# PowerMisc.net
KiCad netlist of a schematic drawn in Altium Designer
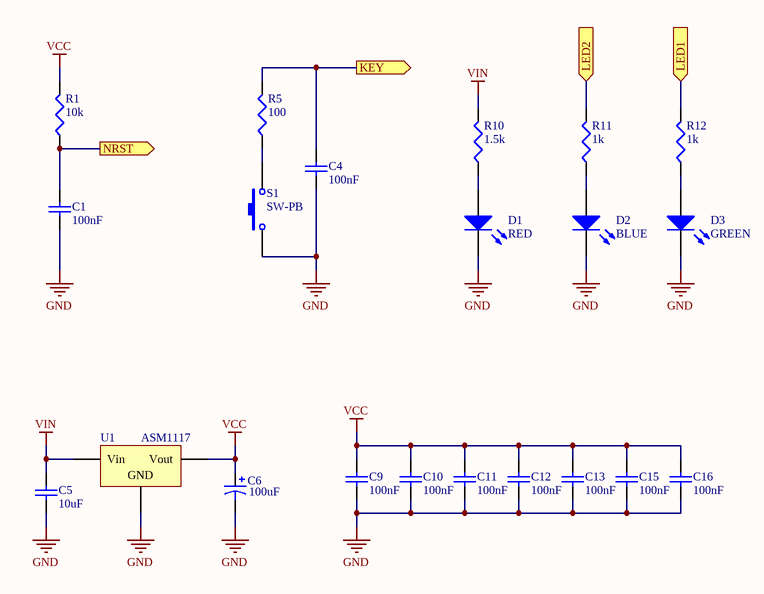
[diagram p0: PowerMisc.SchDoc]

(export (version "E")
  (design (tool "Eeschema 10.0.6"))
  (components
    (comp (ref "C1")
      (value "100nF")
      (footprint "0603C")
      (description "Capacitor")
      (fields (field (name "Comment") "Cap") (field (name "PUBLISHER") "Altium Limited"))
      (libsource (lib "Miscellaneous Devices") (part "Cap"))
    )
    (comp (ref "C4")
      (value "100nF")
      (footprint "0603C")
      (description "Capacitor")
      (fields (field (name "Comment") "Cap") (field (name "PUBLISHER") "Altium Limited"))
      (libsource (lib "Miscellaneous Devices") (part "Cap"))
    )
    (comp (ref "C5")
      (value "10uF")
      (footprint "1206C")
      (description "Capacitor")
      (fields (field (name "Comment") "Cap") (field (name "PUBLISHER") "Altium Limited"))
      (libsource (lib "Miscellaneous Devices") (part "Cap"))
    )
    (comp (ref "C6")
      (value "100uF")
      (footprint "CAP3528T")
      (description "Polarized Capacitor (Surface Mount)")
      (fields (field (name "Comment") "Cap Pol3") (field (name "PUBLISHER") "Altium Limited"))
      (libsource (lib "Miscellaneous Devices") (part "Cap Pol3"))
    )
    (comp (ref "C9")
      (value "100nF")
      (footprint "0603C")
      (description "Capacitor")
      (fields (field (name "Comment") "Cap") (field (name "PUBLISHER") "Altium Limited"))
      (libsource (lib "Miscellaneous Devices") (part "Cap"))
    )
    (comp (ref "C10")
      (value "100nF")
      (footprint "0603C")
      (description "Capacitor")
      (fields (field (name "Comment") "Cap") (field (name "PUBLISHER") "Altium Limited"))
      (libsource (lib "Miscellaneous Devices") (part "Cap"))
    )
    (comp (ref "C11")
      (value "100nF")
      (footprint "0603C")
      (description "Capacitor")
      (fields (field (name "Comment") "Cap") (field (name "PUBLISHER") "Altium Limited"))
      (libsource (lib "Miscellaneous Devices") (part "Cap"))
    )
    (comp (ref "C12")
      (value "100nF")
      (footprint "0603C")
      (description "Capacitor")
      (fields (field (name "Comment") "Cap") (field (name "PUBLISHER") "Altium Limited"))
      (libsource (lib "Miscellaneous Devices") (part "Cap"))
    )
    (comp (ref "C13")
      (value "100nF")
      (footprint "0603C")
      (description "Capacitor")
      (fields (field (name "Comment") "Cap") (field (name "PUBLISHER") "Altium Limited"))
      (libsource (lib "Miscellaneous Devices") (part "Cap"))
    )
    (comp (ref "C15")
      (value "100nF")
      (footprint "0603C")
      (description "Capacitor")
      (fields (field (name "Comment") "Cap") (field (name "PUBLISHER") "Altium Limited"))
      (libsource (lib "Miscellaneous Devices") (part "Cap"))
    )
    (comp (ref "C16")
      (value "100nF")
      (footprint "0603C")
      (description "Capacitor")
      (fields (field (name "Comment") "Cap") (field (name "PUBLISHER") "Altium Limited"))
      (libsource (lib "Miscellaneous Devices") (part "Cap"))
    )
    (comp (ref "D1")
      (value "RED")
      (footprint "0603LED")
      (description "Typical RED GaAs LED")
      (fields (field (name "PUBLISHER") "Altium Limited"))
      (libsource (lib "Miscellaneous Devices") (part "LED1"))
    )
    (comp (ref "D2")
      (value "BLUE")
      (footprint "0603LED")
      (description "Typical RED GaAs LED")
      (fields (field (name "PUBLISHER") "Altium Limited"))
      (libsource (lib "Miscellaneous Devices") (part "LED1"))
    )
    (comp (ref "D3")
      (value "GREEN")
      (footprint "0603LED")
      (description "Typical RED GaAs LED")
      (fields (field (name "PUBLISHER") "Altium Limited"))
      (libsource (lib "Miscellaneous Devices") (part "LED1"))
    )
    (comp (ref "R1")
      (value "10k")
      (footprint "0603R")
      (description "Resistor")
      (fields (field (name "Comment") "Res3") (field (name "PUBLISHER") "Altium Limited"))
      (libsource (lib "Miscellaneous Devices") (part "Res3"))
    )
    (comp (ref "R5")
      (value "100")
      (footprint "0603R")
      (description "Resistor")
      (fields (field (name "Comment") "Res3") (field (name "PUBLISHER") "Altium Limited"))
      (libsource (lib "Miscellaneous Devices") (part "Res3"))
    )
    (comp (ref "R10")
      (value "1.5k")
      (footprint "0603R")
      (description "Resistor")
      (fields (field (name "Comment") "Res3") (field (name "PUBLISHER") "Altium Limited"))
      (libsource (lib "Miscellaneous Devices") (part "Res3"))
    )
    (comp (ref "R11")
      (value "1k")
      (footprint "0603R")
      (description "Resistor")
      (fields (field (name "Comment") "Res3") (field (name "PUBLISHER") "Altium Limited"))
      (libsource (lib "Miscellaneous Devices") (part "Res3"))
    )
    (comp (ref "R12")
      (value "1k")
      (footprint "0603R")
      (description "Resistor")
      (fields (field (name "Comment") "Res3") (field (name "PUBLISHER") "Altium Limited"))
      (libsource (lib "Miscellaneous Devices") (part "Res3"))
    )
    (comp (ref "S1")
      (value "SW-PB")
      (footprint "SPST-SM2")
      (description "Switch")
      (fields (field (name "PUBLISHER") "Altium Limited"))
      (libsource (lib "Miscellaneous Devices") (part "SW-PB"))
    )
    (comp (ref "U1")
      (value "ASM1117")
      (footprint "SOT223")
      (description "Voltage Regulator")
      (fields (field (name "PUBLISHER") "Altium Limited"))
      (libsource (lib "Miscellaneous Devices") (part "Volt Reg"))
    )
  )
  (nets
    (net (code "1") (name "/KEY") (class "Default")
      (node (ref "C4") (pin "1") (pinfunction "1_1") (pintype "passive"))
      (node (ref "R5") (pin "2") (pinfunction "2_2") (pintype "passive"))
    )
    (net (code "2") (name "/LED1") (class "Default")
      (node (ref "R12") (pin "2") (pinfunction "2_2") (pintype "passive"))
    )
    (net (code "3") (name "/LED2") (class "Default")
      (node (ref "R11") (pin "2") (pinfunction "2_2") (pintype "passive"))
    )
    (net (code "4") (name "/NRST") (class "Default")
      (node (ref "C1") (pin "1") (pinfunction "1_1") (pintype "passive"))
      (node (ref "R1") (pin "1") (pinfunction "1_1") (pintype "passive"))
    )
    (net (code "5") (name "GND") (class "Default")
      (node (ref "C1") (pin "2") (pinfunction "2_2") (pintype "passive"))
      (node (ref "C10") (pin "2") (pinfunction "2_2") (pintype "passive"))
      (node (ref "C11") (pin "2") (pinfunction "2_2") (pintype "passive"))
      (node (ref "C12") (pin "2") (pinfunction "2_2") (pintype "passive"))
      (node (ref "C13") (pin "2") (pinfunction "2_2") (pintype "passive"))
      (node (ref "C15") (pin "2") (pinfunction "2_2") (pintype "passive"))
      (node (ref "C16") (pin "2") (pinfunction "2_2") (pintype "passive"))
      (node (ref "C4") (pin "2") (pinfunction "2_2") (pintype "passive"))
      (node (ref "C5") (pin "2") (pinfunction "2_2") (pintype "passive"))
      (node (ref "C6") (pin "2") (pinfunction "2_2") (pintype "passive"))
      (node (ref "C9") (pin "2") (pinfunction "2_2") (pintype "passive"))
      (node (ref "D1") (pin "2") (pinfunction "K_2") (pintype "passive"))
      (node (ref "D2") (pin "2") (pinfunction "K_2") (pintype "passive"))
      (node (ref "D3") (pin "2") (pinfunction "K_2") (pintype "passive"))
      (node (ref "S1") (pin "1") (pinfunction "1_1") (pintype "passive"))
      (node (ref "U1") (pin "2") (pinfunction "GND_2") (pintype "passive"))
    )
    (net (code "6") (name "Net-(D1-A)") (class "Default")
      (node (ref "D1") (pin "1") (pinfunction "A_1") (pintype "passive"))
      (node (ref "R10") (pin "1") (pinfunction "1_1") (pintype "passive"))
    )
    (net (code "7") (name "Net-(D2-A)") (class "Default")
      (node (ref "D2") (pin "1") (pinfunction "A_1") (pintype "passive"))
      (node (ref "R11") (pin "1") (pinfunction "1_1") (pintype "passive"))
    )
    (net (code "8") (name "Net-(D3-A)") (class "Default")
      (node (ref "D3") (pin "1") (pinfunction "A_1") (pintype "passive"))
      (node (ref "R12") (pin "1") (pinfunction "1_1") (pintype "passive"))
    )
    (net (code "9") (name "Net-(R5-Pad1)") (class "Default")
      (node (ref "R5") (pin "1") (pinfunction "1_1") (pintype "passive"))
      (node (ref "S1") (pin "2") (pinfunction "2_2") (pintype "passive"))
    )
    (net (code "10") (name "VCC") (class "Default")
      (node (ref "C10") (pin "1") (pinfunction "1_1") (pintype "passive"))
      (node (ref "C11") (pin "1") (pinfunction "1_1") (pintype "passive"))
      (node (ref "C12") (pin "1") (pinfunction "1_1") (pintype "passive"))
      (node (ref "C13") (pin "1") (pinfunction "1_1") (pintype "passive"))
      (node (ref "C15") (pin "1") (pinfunction "1_1") (pintype "passive"))
      (node (ref "C16") (pin "1") (pinfunction "1_1") (pintype "passive"))
      (node (ref "C6") (pin "1") (pinfunction "1_1") (pintype "passive"))
      (node (ref "C9") (pin "1") (pinfunction "1_1") (pintype "passive"))
      (node (ref "R1") (pin "2") (pinfunction "2_2") (pintype "passive"))
      (node (ref "U1") (pin "3") (pinfunction "Vout_3") (pintype "passive"))
    )
    (net (code "11") (name "VIN") (class "Default")
      (node (ref "C5") (pin "1") (pinfunction "1_1") (pintype "passive"))
      (node (ref "R10") (pin "2") (pinfunction "2_2") (pintype "passive"))
      (node (ref "U1") (pin "1") (pinfunction "Vin_1") (pintype "passive"))
    )
  )
)
